# SoftstartEmbedded.net
KiCad netlist of a schematic drawn in EAGLE
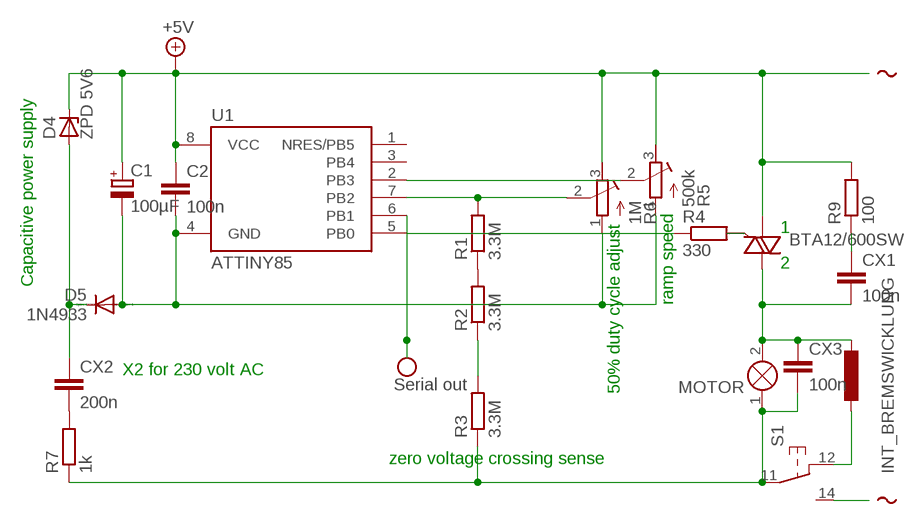
[diagram p0: schematic, sheet 1]

(export (version "E")
  (design (tool "Eeschema 10.0.6"))
  (components
    (comp (ref "BTA12/600SW")
      (value "BT138-H")
      (footprint "eagle-import:TO220BH")
      (libsource (lib "eagle-import") (part "BT138-H"))
    )
    (comp (ref "C1")
      (value "100µF")
      (footprint "eagle-import:E7,5-16")
      (libsource (lib "eagle-import") (part "CPOL-EUE7.5-16"))
    )
    (comp (ref "C2")
      (value "100n")
      (footprint "eagle-import:C025-025X050")
      (libsource (lib "eagle-import") (part "C-EU025-025X050"))
    )
    (comp (ref "CX1")
      (value "100n")
      (footprint "eagle-import:XC15B5")
      (libsource (lib "eagle-import") (part "CXXC15B5"))
    )
    (comp (ref "CX2")
      (value "200n")
      (footprint "eagle-import:XC15B5")
      (libsource (lib "eagle-import") (part "CXXC15B5"))
    )
    (comp (ref "CX3")
      (value "100n")
      (footprint "eagle-import:XC15B5")
      (libsource (lib "eagle-import") (part "CXXC15B5"))
    )
    (comp (ref "D4")
      (value "ZPD 5V6")
      (footprint "eagle-import:DO35Z10")
      (libsource (lib "eagle-import") (part "ZPD"))
    )
    (comp (ref "D5")
      (value "1N4933")
      (footprint "eagle-import:DO41-10")
      (libsource (lib "eagle-import") (part "1N4933"))
    )
    (comp (ref "INT_BREMSWICKLUNG")
      (value "L-EUIR-2")
      (footprint "eagle-import:IR-2")
      (libsource (lib "eagle-import") (part "L-EUIR-2"))
    )
    (comp (ref "MOTOR")
      (value "SIGNALLAMPE")
      (footprint "eagle-import:LAMPE")
      (libsource (lib "eagle-import") (part "SIGNALLAMPE"))
    )
    (comp (ref "R1")
      (value "3.3M")
      (footprint "eagle-import:0207_10")
      (libsource (lib "eagle-import") (part "R-EU_0207/10"))
    )
    (comp (ref "R2")
      (value "3.3M")
      (footprint "eagle-import:0207_10")
      (libsource (lib "eagle-import") (part "R-EU_0207/10"))
    )
    (comp (ref "R3")
      (value "3.3M")
      (footprint "eagle-import:0207_10")
      (libsource (lib "eagle-import") (part "R-EU_0207/10"))
    )
    (comp (ref "R4")
      (value "330")
      (footprint "eagle-import:0207_10")
      (libsource (lib "eagle-import") (part "R-EU_0207/10"))
    )
    (comp (ref "R5")
      (value "500k")
      (footprint "eagle-import:RTRIM4G_J")
      (libsource (lib "eagle-import") (part "R-TRIMM4G/J"))
    )
    (comp (ref "R6")
      (value "1M")
      (footprint "eagle-import:RTRIM4G_J")
      (libsource (lib "eagle-import") (part "R-TRIMM4G/J"))
    )
    (comp (ref "R7")
      (value "1k")
      (footprint "eagle-import:0207_10")
      (libsource (lib "eagle-import") (part "R-EU_0207/10"))
    )
    (comp (ref "R9")
      (value "100")
      (footprint "eagle-import:0207_10")
      (libsource (lib "eagle-import") (part "R-EU_0207/10"))
    )
    (comp (ref "S1")
      (value "DRUCK-WECHSELSCHALTER")
      (footprint "eagle-import:DRUCK-WECHSELSCHALTER")
      (libsource (lib "eagle-import") (part "DRUCK-WECHSELSCHALTER"))
    )
    (comp (ref "U1")
      (value "ATTINY85")
      (footprint "eagle-import:PDIP08_300MIL")
      (libsource (lib "eagle-import") (part "ATTINY85PV-10"))
    )
  )
  (nets
    (net (code "1") (name "+5V") (class "Default")
      (node (ref "BTA12/600SW") (pin "T1") (pinfunction "A1_T1") (pintype "passive"))
      (node (ref "C1") (pin "+") (pinfunction "+_+") (pintype "passive"))
      (node (ref "C2") (pin "1") (pinfunction "1_1") (pintype "passive"))
      (node (ref "D4") (pin "C") (pinfunction "C_C") (pintype "passive"))
      (node (ref "R5") (pin "3") (pinfunction "E_3") (pintype "passive"))
      (node (ref "R6") (pin "3") (pinfunction "E_3") (pintype "passive"))
      (node (ref "R9") (pin "2") (pinfunction "2_2") (pintype "passive"))
      (node (ref "U1") (pin "8") (pinfunction "VCC_8") (pintype "power_in"))
    )
    (net (code "2") (name "Net-(BTA12/600SW-A2)") (class "Default")
      (node (ref "BTA12/600SW") (pin "T2") (pinfunction "A2_T2") (pintype "passive"))
      (node (ref "CX1") (pin "2") (pinfunction "2_2") (pintype "passive"))
      (node (ref "CX3") (pin "1") (pinfunction "1_1") (pintype "passive"))
      (node (ref "INT_BREMSWICKLUNG") (pin "1") (pinfunction "1_1") (pintype "passive"))
      (node (ref "MOTOR") (pin "2") (pinfunction "X2_2") (pintype "passive"))
    )
    (net (code "3") (name "Net-(BTA12/600SW-PadG)") (class "Default")
      (node (ref "BTA12/600SW") (pin "G") (pinfunction "G_G") (pintype "passive"))
      (node (ref "R4") (pin "2") (pinfunction "2_2") (pintype "passive"))
    )
    (net (code "4") (name "Net-(CX1-Pad1)") (class "Default")
      (node (ref "CX1") (pin "1") (pinfunction "1_1") (pintype "passive"))
      (node (ref "R9") (pin "1") (pinfunction "1_1") (pintype "passive"))
    )
    (net (code "5") (name "Net-(CX2-Pad1)") (class "Default")
      (node (ref "CX2") (pin "1") (pinfunction "1_1") (pintype "passive"))
      (node (ref "D4") (pin "A") (pinfunction "A_A") (pintype "passive"))
      (node (ref "D5") (pin "C") (pinfunction "C_C") (pintype "passive"))
    )
    (net (code "6") (name "Net-(CX2-Pad2)") (class "Default")
      (node (ref "CX2") (pin "2") (pinfunction "2_2") (pintype "passive"))
      (node (ref "R7") (pin "2") (pinfunction "2_2") (pintype "passive"))
    )
    (net (code "7") (name "Net-(INT_BREMSWICKLUNG-Pad2)") (class "Default")
      (node (ref "INT_BREMSWICKLUNG") (pin "2") (pinfunction "2_2") (pintype "passive"))
      (node (ref "S1") (pin "12") (pinfunction "12_12") (pintype "passive"))
    )
    (net (code "8") (name "Net-(MOTOR-X1)") (class "Default")
      (node (ref "CX3") (pin "2") (pinfunction "2_2") (pintype "passive"))
      (node (ref "MOTOR") (pin "1") (pinfunction "X1_1") (pintype "passive"))
      (node (ref "R3") (pin "1") (pinfunction "1_1") (pintype "passive"))
      (node (ref "R7") (pin "1") (pinfunction "1_1") (pintype "passive"))
      (node (ref "S1") (pin "11") (pinfunction "11_11") (pintype "passive"))
    )
    (net (code "9") (name "Net-(R1-Pad1)") (class "Default")
      (node (ref "R1") (pin "1") (pinfunction "1_1") (pintype "passive"))
      (node (ref "R2") (pin "2") (pinfunction "2_2") (pintype "passive"))
    )
    (net (code "10") (name "Net-(R2-Pad1)") (class "Default")
      (node (ref "R2") (pin "1") (pinfunction "1_1") (pintype "passive"))
      (node (ref "R3") (pin "2") (pinfunction "2_2") (pintype "passive"))
    )
    (net (code "11") (name "Net-(R5-A)") (class "Default")
      (node (ref "C1") (pin "-") (pinfunction "-_-") (pintype "passive"))
      (node (ref "C2") (pin "2") (pinfunction "2_2") (pintype "passive"))
      (node (ref "D5") (pin "A") (pinfunction "A_A") (pintype "passive"))
      (node (ref "R5") (pin "1") (pinfunction "A_1") (pintype "passive"))
      (node (ref "R6") (pin "1") (pinfunction "A_1") (pintype "passive"))
      (node (ref "U1") (pin "4") (pinfunction "GND_4") (pintype "power_in"))
    )
    (net (code "12") (name "Net-(R5-S)") (class "Default")
      (node (ref "R5") (pin "2") (pinfunction "S_2") (pintype "passive"))
      (node (ref "U1") (pin "2") (pinfunction "PB3_2") (pintype "bidirectional"))
    )
    (net (code "13") (name "Net-(R6-S)") (class "Default")
      (node (ref "R1") (pin "2") (pinfunction "2_2") (pintype "passive"))
      (node (ref "R6") (pin "2") (pinfunction "S_2") (pintype "passive"))
      (node (ref "U1") (pin "7") (pinfunction "PB2_7") (pintype "bidirectional"))
    )
    (net (code "14") (name "Net-(U1-PB0)") (class "Default")
      (node (ref "R4") (pin "1") (pinfunction "1_1") (pintype "passive"))
      (node (ref "U1") (pin "5") (pinfunction "PB0_5") (pintype "bidirectional"))
    )
    (net (code "15") (name "Serial out") (class "Default")
      (node (ref "U1") (pin "6") (pinfunction "PB1_6") (pintype "bidirectional"))
    )
    (net (code "16") (name "unconnected-(S1-Pad14)") (class "Default")
      (node (ref "S1") (pin "14") (pinfunction "14_14") (pintype "passive"))
    )
    (net (code "17") (name "unconnected-(U1-NRES{slash}PB5-Pad1)") (class "Default")
      (node (ref "U1") (pin "1") (pinfunction "NRES/PB5_1") (pintype "bidirectional"))
    )
    (net (code "18") (name "unconnected-(U1-PB4-Pad3)") (class "Default")
      (node (ref "U1") (pin "3") (pinfunction "PB4_3") (pintype "bidirectional"))
    )
  )
)
